# mcu.net
KiCad netlist of a schematic drawn in Altium Designer
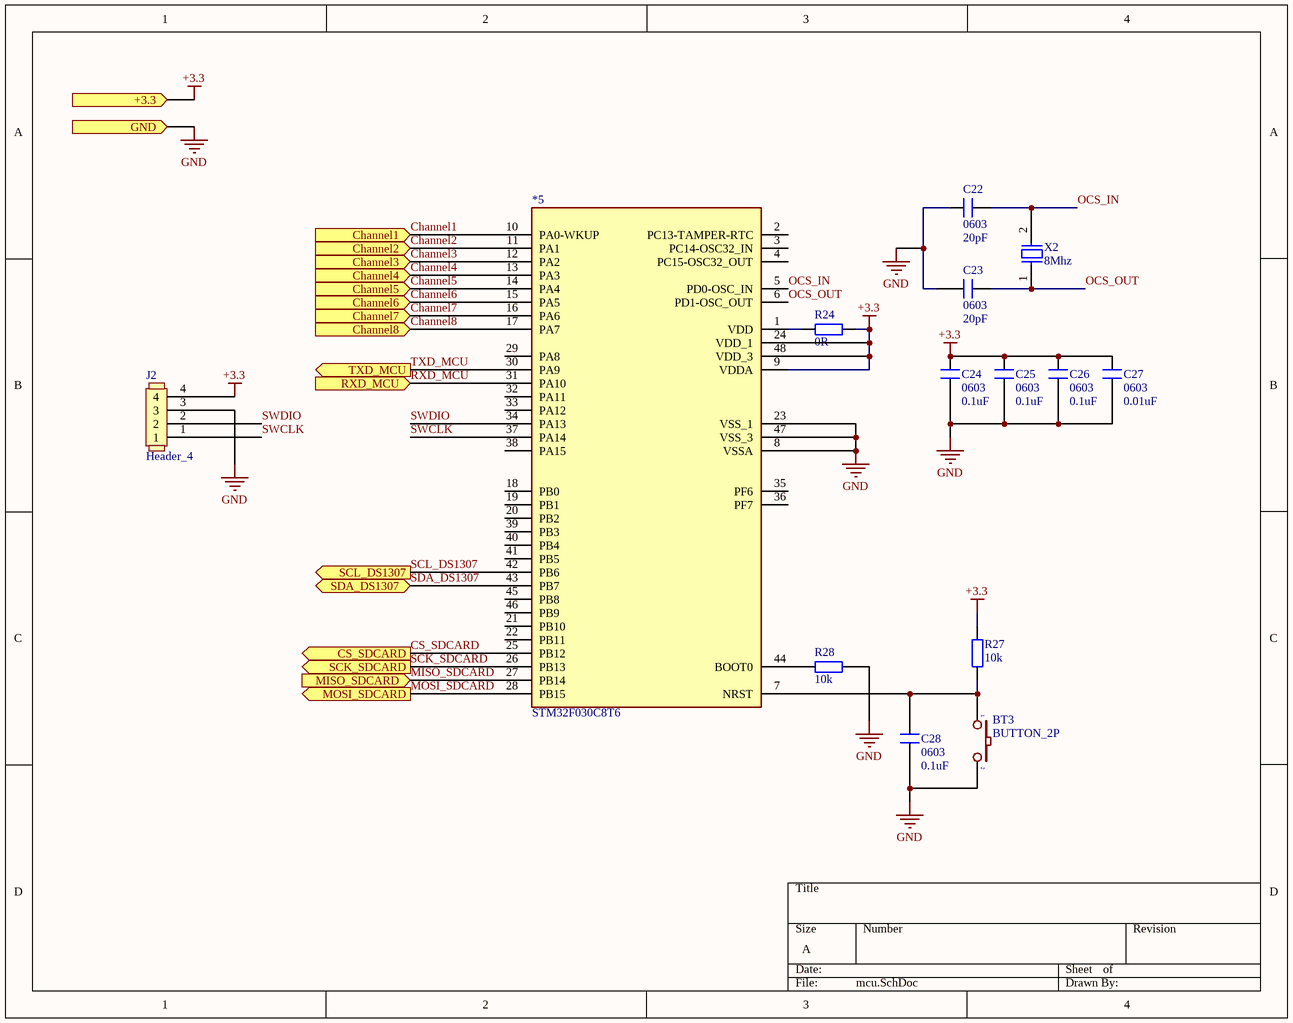
[diagram p0: mcu.SchDoc]

(export (version "E")
  (design (tool "Eeschema 10.0.6"))
  (components
    (comp (ref "*5")
      (value "STM32F030C8T6")
      (footprint "STM32_LQPF48")
      (libsource (lib "TrungVan_Lib") (part "STM32F030C8T6"))
    )
    (comp (ref "BT3")
      (value "BUTTON_2P")
      (footprint "BUTTON_2P_SMD")
      (fields (field (name "MANUFACTURER") "C&K") (field (name "PART NUMBER") "PTS636 SM25F SMTR LFS"))
      (libsource (lib "S2000_Electromechanical") (part "BUTTON_2P"))
    )
    (comp (ref "C22")
      (value "0603")
      (footprint "C_0603")
      (description "Ceramic Capacitor 0603  (+-10% TH)/(+10%SMD)")
      (fields
        (field (name "MANUFACTURER") "Murata Electronics")
        (field (name "PART NUMBER") "GRM1885C1H180JA01J")
        (field (name "ALTIUM_VALUE") "20pF")
      )
      (libsource (lib "S1200_Capacitor") (part "Cap_Cer_0603_18pF"))
    )
    (comp (ref "C23")
      (value "0603")
      (footprint "C_0603")
      (description "Ceramic Capacitor 0603  (+-10% TH)/(+10%SMD)")
      (fields
        (field (name "MANUFACTURER") "Murata Electronics")
        (field (name "PART NUMBER") "GRM1885C1H180JA01J")
        (field (name "ALTIUM_VALUE") "20pF")
      )
      (libsource (lib "S1200_Capacitor") (part "Cap_Cer_0603_18pF"))
    )
    (comp (ref "C24")
      (value "0603")
      (footprint "C_0603")
      (description "Ceramic Capacitor 0603  (+-10% TH)/(+10%SMD)")
      (fields
        (field (name "MANUFACTURER") "Murata Electronics")
        (field (name "PART NUMBER") "GCM188R91E104KA37J")
        (field (name "ALTIUM_VALUE") "0.1uF")
      )
      (libsource (lib "S1200_Capacitor") (part "Cap_Cer_0603_0.1uF_25V"))
    )
    (comp (ref "C25")
      (value "0603")
      (footprint "C_0603")
      (description "Ceramic Capacitor 0603  (+-10% TH)/(+10%SMD)")
      (fields
        (field (name "MANUFACTURER") "Murata Electronics")
        (field (name "PART NUMBER") "GCM188R91E104KA37J")
        (field (name "ALTIUM_VALUE") "0.1uF")
      )
      (libsource (lib "S1200_Capacitor") (part "Cap_Cer_0603_0.1uF_25V"))
    )
    (comp (ref "C26")
      (value "0603")
      (footprint "C_0603")
      (description "Ceramic Capacitor 0603  (+-10% TH)/(+10%SMD)")
      (fields
        (field (name "MANUFACTURER") "Murata Electronics")
        (field (name "PART NUMBER") "GCM188R91E104KA37J")
        (field (name "ALTIUM_VALUE") "0.1uF")
      )
      (libsource (lib "S1200_Capacitor") (part "Cap_Cer_0603_0.1uF_25V"))
    )
    (comp (ref "C27")
      (value "0603")
      (footprint "C_0603")
      (description "Ceramic Capacitor 0603  (+-10% TH)/(+10%SMD)")
      (fields
        (field (name "MANUFACTURER") "Murata Electronics")
        (field (name "PART NUMBER") "GCM188R91E104KA37J")
        (field (name "ALTIUM_VALUE") "0.01uF")
      )
      (libsource (lib "S1200_Capacitor") (part "Cap_Cer_0603_0.1uF_25V"))
    )
    (comp (ref "C28")
      (value "0603")
      (footprint "C_0603")
      (description "Ceramic Capacitor 0603  (+-10% TH)/(+10%SMD)")
      (fields
        (field (name "MANUFACTURER") "Murata Electronics")
        (field (name "PART NUMBER") "GCM188R91E104KA37J")
        (field (name "ALTIUM_VALUE") "0.1uF")
      )
      (libsource (lib "S1200_Capacitor") (part "Cap_Cer_0603_0.1uF_25V"))
    )
    (comp (ref "J2")
      (value "Header_4")
      (footprint "HEADER_4_2P54_SHROUDED")
      (libsource (lib "S1900_Connector") (part "Header_4"))
    )
    (comp (ref "R24")
      (value "0R")
      (footprint "tro smd 0603")
      (description "Dán")
      (libsource (lib "TrungVan_Lib") (part "Tro 0805 5% 0R"))
    )
    (comp (ref "R27")
      (value "10k")
      (footprint "tro smd 0805")
      (description "Dán")
      (libsource (lib "TrungVan_Lib") (part "Tro 0805 5% 10k"))
    )
    (comp (ref "R28")
      (value "10k")
      (footprint "tro smd 0805")
      (description "Dán")
      (libsource (lib "TrungVan_Lib") (part "Tro 0805 5% 10k"))
    )
    (comp (ref "X2")
      (value "8Mhz")
      (footprint "XTAL_SMD_3P5")
      (description "Use for 8Mhz")
      (fields (field (name "MANUFACTURER") "WTL") (field (name "PART NUMBER") "WTL5G11651"))
      (libsource (lib "S1600_Crystal_Oscillator") (part "Xtal_2P_SMD_5P0X3P5_8Mhz"))
    )
  )
  (nets
    (net (code "1") (name "+3.3") (class "Default")
      (node (ref "*5") (pin "24") (pinfunction "VDD_1_24") (pintype "passive"))
      (node (ref "*5") (pin "48") (pinfunction "VDD_3_48") (pintype "passive"))
      (node (ref "*5") (pin "9") (pinfunction "VDDA_9") (pintype "passive"))
      (node (ref "C24") (pin "2") (pinfunction "2_2") (pintype "passive"))
      (node (ref "C25") (pin "2") (pinfunction "2_2") (pintype "passive"))
      (node (ref "C26") (pin "2") (pinfunction "2_2") (pintype "passive"))
      (node (ref "C27") (pin "2") (pinfunction "2_2") (pintype "passive"))
      (node (ref "J2") (pin "4") (pinfunction "4_4") (pintype "passive"))
      (node (ref "R24") (pin "1") (pinfunction "1_1") (pintype "passive"))
      (node (ref "R27") (pin "2") (pinfunction "2_2") (pintype "passive"))
    )
    (net (code "2") (name "/CS_SDCARD") (class "Default")
      (node (ref "*5") (pin "25") (pinfunction "PB12_25") (pintype "passive"))
    )
    (net (code "3") (name "/Channel1") (class "Default")
      (node (ref "*5") (pin "10") (pinfunction "PA0-WKUP_10") (pintype "passive"))
    )
    (net (code "4") (name "/Channel2") (class "Default")
      (node (ref "*5") (pin "11") (pinfunction "PA1_11") (pintype "passive"))
    )
    (net (code "5") (name "/Channel3") (class "Default")
      (node (ref "*5") (pin "12") (pinfunction "PA2_12") (pintype "passive"))
    )
    (net (code "6") (name "/Channel4") (class "Default")
      (node (ref "*5") (pin "13") (pinfunction "PA3_13") (pintype "passive"))
    )
    (net (code "7") (name "/Channel5") (class "Default")
      (node (ref "*5") (pin "14") (pinfunction "PA4_14") (pintype "passive"))
    )
    (net (code "8") (name "/Channel6") (class "Default")
      (node (ref "*5") (pin "15") (pinfunction "PA5_15") (pintype "passive"))
    )
    (net (code "9") (name "/Channel7") (class "Default")
      (node (ref "*5") (pin "16") (pinfunction "PA6_16") (pintype "passive"))
    )
    (net (code "10") (name "/Channel8") (class "Default")
      (node (ref "*5") (pin "17") (pinfunction "PA7_17") (pintype "passive"))
    )
    (net (code "11") (name "/MISO_SDCARD") (class "Default")
      (node (ref "*5") (pin "27") (pinfunction "PB14_27") (pintype "passive"))
    )
    (net (code "12") (name "/MOSI_SDCARD") (class "Default")
      (node (ref "*5") (pin "28") (pinfunction "PB15_28") (pintype "passive"))
    )
    (net (code "13") (name "/OCS_IN") (class "Default")
      (node (ref "*5") (pin "5") (pinfunction "PD0-OSC_IN_5") (pintype "passive"))
      (node (ref "C22") (pin "1") (pinfunction "1_1") (pintype "passive"))
      (node (ref "X2") (pin "2") (pinfunction "2_2") (pintype "passive"))
    )
    (net (code "14") (name "/OCS_OUT") (class "Default")
      (node (ref "*5") (pin "6") (pinfunction "PD1-OSC_OUT_6") (pintype "passive"))
      (node (ref "C23") (pin "1") (pinfunction "1_1") (pintype "passive"))
      (node (ref "X2") (pin "1") (pinfunction "1_1") (pintype "passive"))
    )
    (net (code "15") (name "/RXD_MCU") (class "Default")
      (node (ref "*5") (pin "31") (pinfunction "PA10_31") (pintype "passive"))
    )
    (net (code "16") (name "/SCK_SDCARD") (class "Default")
      (node (ref "*5") (pin "26") (pinfunction "PB13_26") (pintype "passive"))
    )
    (net (code "17") (name "/SCL_DS1307") (class "Default")
      (node (ref "*5") (pin "42") (pinfunction "PB6_42") (pintype "passive"))
    )
    (net (code "18") (name "/SDA_DS1307") (class "Default")
      (node (ref "*5") (pin "43") (pinfunction "PB7_43") (pintype "passive"))
    )
    (net (code "19") (name "/SWCLK") (class "Default")
      (node (ref "*5") (pin "37") (pinfunction "PA14_37") (pintype "passive"))
      (node (ref "J2") (pin "1") (pinfunction "1_1") (pintype "passive"))
    )
    (net (code "20") (name "/SWDIO") (class "Default")
      (node (ref "*5") (pin "34") (pinfunction "PA13_34") (pintype "passive"))
      (node (ref "J2") (pin "2") (pinfunction "2_2") (pintype "passive"))
    )
    (net (code "21") (name "/TXD_MCU") (class "Default")
      (node (ref "*5") (pin "30") (pinfunction "PA9_30") (pintype "passive"))
    )
    (net (code "22") (name "GND") (class "Default")
      (node (ref "*5") (pin "23") (pinfunction "VSS_1_23") (pintype "passive"))
      (node (ref "*5") (pin "47") (pinfunction "VSS_3_47") (pintype "passive"))
      (node (ref "*5") (pin "8") (pinfunction "VSSA_8") (pintype "passive"))
      (node (ref "BT3") (pin "2") (pinfunction "2_2") (pintype "passive"))
      (node (ref "C22") (pin "2") (pinfunction "2_2") (pintype "passive"))
      (node (ref "C23") (pin "2") (pinfunction "2_2") (pintype "passive"))
      (node (ref "C24") (pin "1") (pinfunction "1_1") (pintype "passive"))
      (node (ref "C25") (pin "1") (pinfunction "1_1") (pintype "passive"))
      (node (ref "C26") (pin "1") (pinfunction "1_1") (pintype "passive"))
      (node (ref "C27") (pin "1") (pinfunction "1_1") (pintype "passive"))
      (node (ref "C28") (pin "1") (pinfunction "1_1") (pintype "passive"))
      (node (ref "J2") (pin "3") (pinfunction "3_3") (pintype "passive"))
      (node (ref "R28") (pin "1") (pinfunction "1_1") (pintype "passive"))
    )
    (net (code "23") (name "Net-(*5-BOOT0)") (class "Default")
      (node (ref "*5") (pin "44") (pinfunction "BOOT0_44") (pintype "passive"))
      (node (ref "R28") (pin "2") (pinfunction "2_2") (pintype "passive"))
    )
    (net (code "24") (name "Net-(*5-NRST)") (class "Default")
      (node (ref "*5") (pin "7") (pinfunction "NRST_7") (pintype "passive"))
      (node (ref "BT3") (pin "1") (pinfunction "1_1") (pintype "passive"))
      (node (ref "C28") (pin "2") (pinfunction "2_2") (pintype "passive"))
      (node (ref "R27") (pin "1") (pinfunction "1_1") (pintype "passive"))
    )
    (net (code "25") (name "Net-(*5-VDD)") (class "Default")
      (node (ref "*5") (pin "1") (pinfunction "VDD_1") (pintype "passive"))
      (node (ref "R24") (pin "2") (pinfunction "2_2") (pintype "passive"))
    )
    (net (code "26") (name "unconnected-(*5-PA8-Pad29)") (class "Default")
      (node (ref "*5") (pin "29") (pinfunction "PA8_29") (pintype "passive"))
    )
    (net (code "27") (name "unconnected-(*5-PA11-Pad32)") (class "Default")
      (node (ref "*5") (pin "32") (pinfunction "PA11_32") (pintype "passive"))
    )
    (net (code "28") (name "unconnected-(*5-PA12-Pad33)") (class "Default")
      (node (ref "*5") (pin "33") (pinfunction "PA12_33") (pintype "passive"))
    )
    (net (code "29") (name "unconnected-(*5-PA15-Pad38)") (class "Default")
      (node (ref "*5") (pin "38") (pinfunction "PA15_38") (pintype "passive"))
    )
    (net (code "30") (name "unconnected-(*5-PB0-Pad18)") (class "Default")
      (node (ref "*5") (pin "18") (pinfunction "PB0_18") (pintype "passive"))
    )
    (net (code "31") (name "unconnected-(*5-PB1-Pad19)") (class "Default")
      (node (ref "*5") (pin "19") (pinfunction "PB1_19") (pintype "passive"))
    )
    (net (code "32") (name "unconnected-(*5-PB2-Pad20)") (class "Default")
      (node (ref "*5") (pin "20") (pinfunction "PB2_20") (pintype "passive"))
    )
    (net (code "33") (name "unconnected-(*5-PB3-Pad39)") (class "Default")
      (node (ref "*5") (pin "39") (pinfunction "PB3_39") (pintype "passive"))
    )
    (net (code "34") (name "unconnected-(*5-PB4-Pad40)") (class "Default")
      (node (ref "*5") (pin "40") (pinfunction "PB4_40") (pintype "passive"))
    )
    (net (code "35") (name "unconnected-(*5-PB5-Pad41)") (class "Default")
      (node (ref "*5") (pin "41") (pinfunction "PB5_41") (pintype "passive"))
    )
    (net (code "36") (name "unconnected-(*5-PB8-Pad45)") (class "Default")
      (node (ref "*5") (pin "45") (pinfunction "PB8_45") (pintype "passive"))
    )
    (net (code "37") (name "unconnected-(*5-PB9-Pad46)") (class "Default")
      (node (ref "*5") (pin "46") (pinfunction "PB9_46") (pintype "passive"))
    )
    (net (code "38") (name "unconnected-(*5-PB10-Pad21)") (class "Default")
      (node (ref "*5") (pin "21") (pinfunction "PB10_21") (pintype "passive"))
    )
    (net (code "39") (name "unconnected-(*5-PB11-Pad22)") (class "Default")
      (node (ref "*5") (pin "22") (pinfunction "PB11_22") (pintype "passive"))
    )
    (net (code "40") (name "unconnected-(*5-PC13-TAMPER-RTC-Pad2)") (class "Default")
      (node (ref "*5") (pin "2") (pinfunction "PC13-TAMPER-RTC_2") (pintype "passive"))
    )
    (net (code "41") (name "unconnected-(*5-PC14-OSC32_IN-Pad3)") (class "Default")
      (node (ref "*5") (pin "3") (pinfunction "PC14-OSC32_IN_3") (pintype "passive"))
    )
    (net (code "42") (name "unconnected-(*5-PC15-OSC32_OUT-Pad4)") (class "Default")
      (node (ref "*5") (pin "4") (pinfunction "PC15-OSC32_OUT_4") (pintype "passive"))
    )
    (net (code "43") (name "unconnected-(*5-PF6-Pad35)") (class "Default")
      (node (ref "*5") (pin "35") (pinfunction "PF6_35") (pintype "passive"))
    )
    (net (code "44") (name "unconnected-(*5-PF7-Pad36)") (class "Default")
      (node (ref "*5") (pin "36") (pinfunction "PF7_36") (pintype "passive"))
    )
  )
)
